# MicroSD_SPI_Interface.net
KiCad netlist of a schematic drawn in Altium Designer
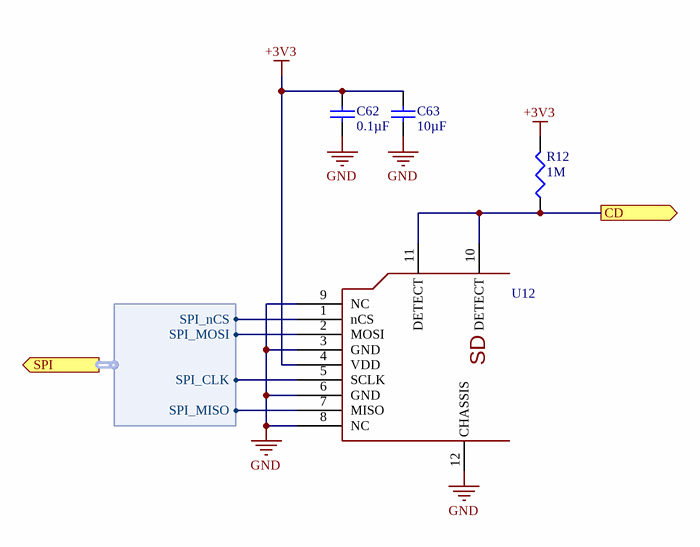
[diagram p0: MicroSD SPI Interface.SchDoc]

(export (version "E")
  (design (tool "Eeschema 10.0.6"))
  (components
    (comp (ref "C62")
      (value "0.1µF")
      (footprint "TDK-CGA2B")
      (description "CAP CER 0.1UF 50V X7R 0402")
      (fields
        (field (name "PART NUMBER") "PC-TDK-02259")
        (field (name "MANUFACTURER PART NUMBER") "CGA2B3X7R1H104K050BB")
        (field (name "PUBLISHER") "AlbertaSat")
      )
      (libsource (lib "Database") (part "Cap"))
    )
    (comp (ref "C63")
      (value "10µF")
      (footprint "TDK-CGA5L")
      (description "CAP CER 10UF 25V X7R 1206")
      (fields
        (field (name "PART NUMBER") "PC-TDK-02917")
        (field (name "MANUFACTURER PART NUMBER") "CGA5L1X7R1E106K160AC")
        (field (name "PUBLISHER") "AlbertaSat")
      )
      (libsource (lib "Database") (part "Cap"))
    )
    (comp (ref "R12")
      (value "1M")
      (footprint "PANA-ERJ6EN")
      (description "RES SMD 1M OHM 1% 1/8W 0805")
      (fields
        (field (name "PART NUMBER") "19707")
        (field (name "MANUFACTURER PART NUMBER") "ERJ-6ENF1004V")
        (field (name "PUBLISHER") "Altium Limited")
      )
      (libsource (lib "Database") (part "Res3"))
    )
    (comp (ref "U12")
      (value "693063010911")
      (footprint "WL-693063010911")
      (description "CONN SD CARD PUSH-PULL R/A SMD")
      (fields (field (name "PART NUMBER") "56"))
      (libsource (lib "Database") (part "693063010911"))
    )
  )
  (nets
    (net (code "2") (name "+3V3") (class "Default")
      (node (ref "C62") (pin "1") (pinfunction "1_1") (pintype "passive"))
      (node (ref "C63") (pin "1") (pinfunction "1_1") (pintype "passive"))
      (node (ref "R12") (pin "2") (pinfunction "2_2") (pintype "passive"))
      (node (ref "U12") (pin "4") (pinfunction "VDD_4") (pintype "passive"))
    )
    (net (code "3") (name "/CD") (class "Default")
      (node (ref "R12") (pin "1") (pinfunction "1_1") (pintype "passive"))
      (node (ref "U12") (pin "10") (pinfunction "DETECT_10") (pintype "passive"))
      (node (ref "U12") (pin "11") (pinfunction "DETECT_11") (pintype "passive"))
    )
    (net (code "4") (name "/SPI_CLK") (class "Default")
      (node (ref "U12") (pin "5") (pinfunction "SCLK_5") (pintype "passive"))
    )
    (net (code "5") (name "/SPI_MISO") (class "Default")
      (node (ref "U12") (pin "7") (pinfunction "MISO_7") (pintype "passive"))
    )
    (net (code "6") (name "/SPI_MOSI") (class "Default")
      (node (ref "U12") (pin "2") (pinfunction "MOSI_2") (pintype "passive"))
    )
    (net (code "7") (name "/SPI_nCS") (class "Default")
      (node (ref "U12") (pin "1") (pinfunction "nCS_1") (pintype "passive"))
    )
    (net (code "9") (name "GND") (class "Default")
      (node (ref "C62") (pin "2") (pinfunction "2_2") (pintype "passive"))
      (node (ref "C63") (pin "2") (pinfunction "2_2") (pintype "passive"))
      (node (ref "U12") (pin "12") (pinfunction "CHASSIS_12") (pintype "passive"))
      (node (ref "U12") (pin "3") (pinfunction "GND_3") (pintype "passive"))
      (node (ref "U12") (pin "6") (pinfunction "GND_6") (pintype "passive"))
      (node (ref "U12") (pin "8") (pinfunction "NC_8") (pintype "passive"))
      (node (ref "U12") (pin "9") (pinfunction "NC_9") (pintype "passive"))
    )
  )
)
